# bottom-pcb.net
KiCad netlist of a schematic drawn in EAGLE
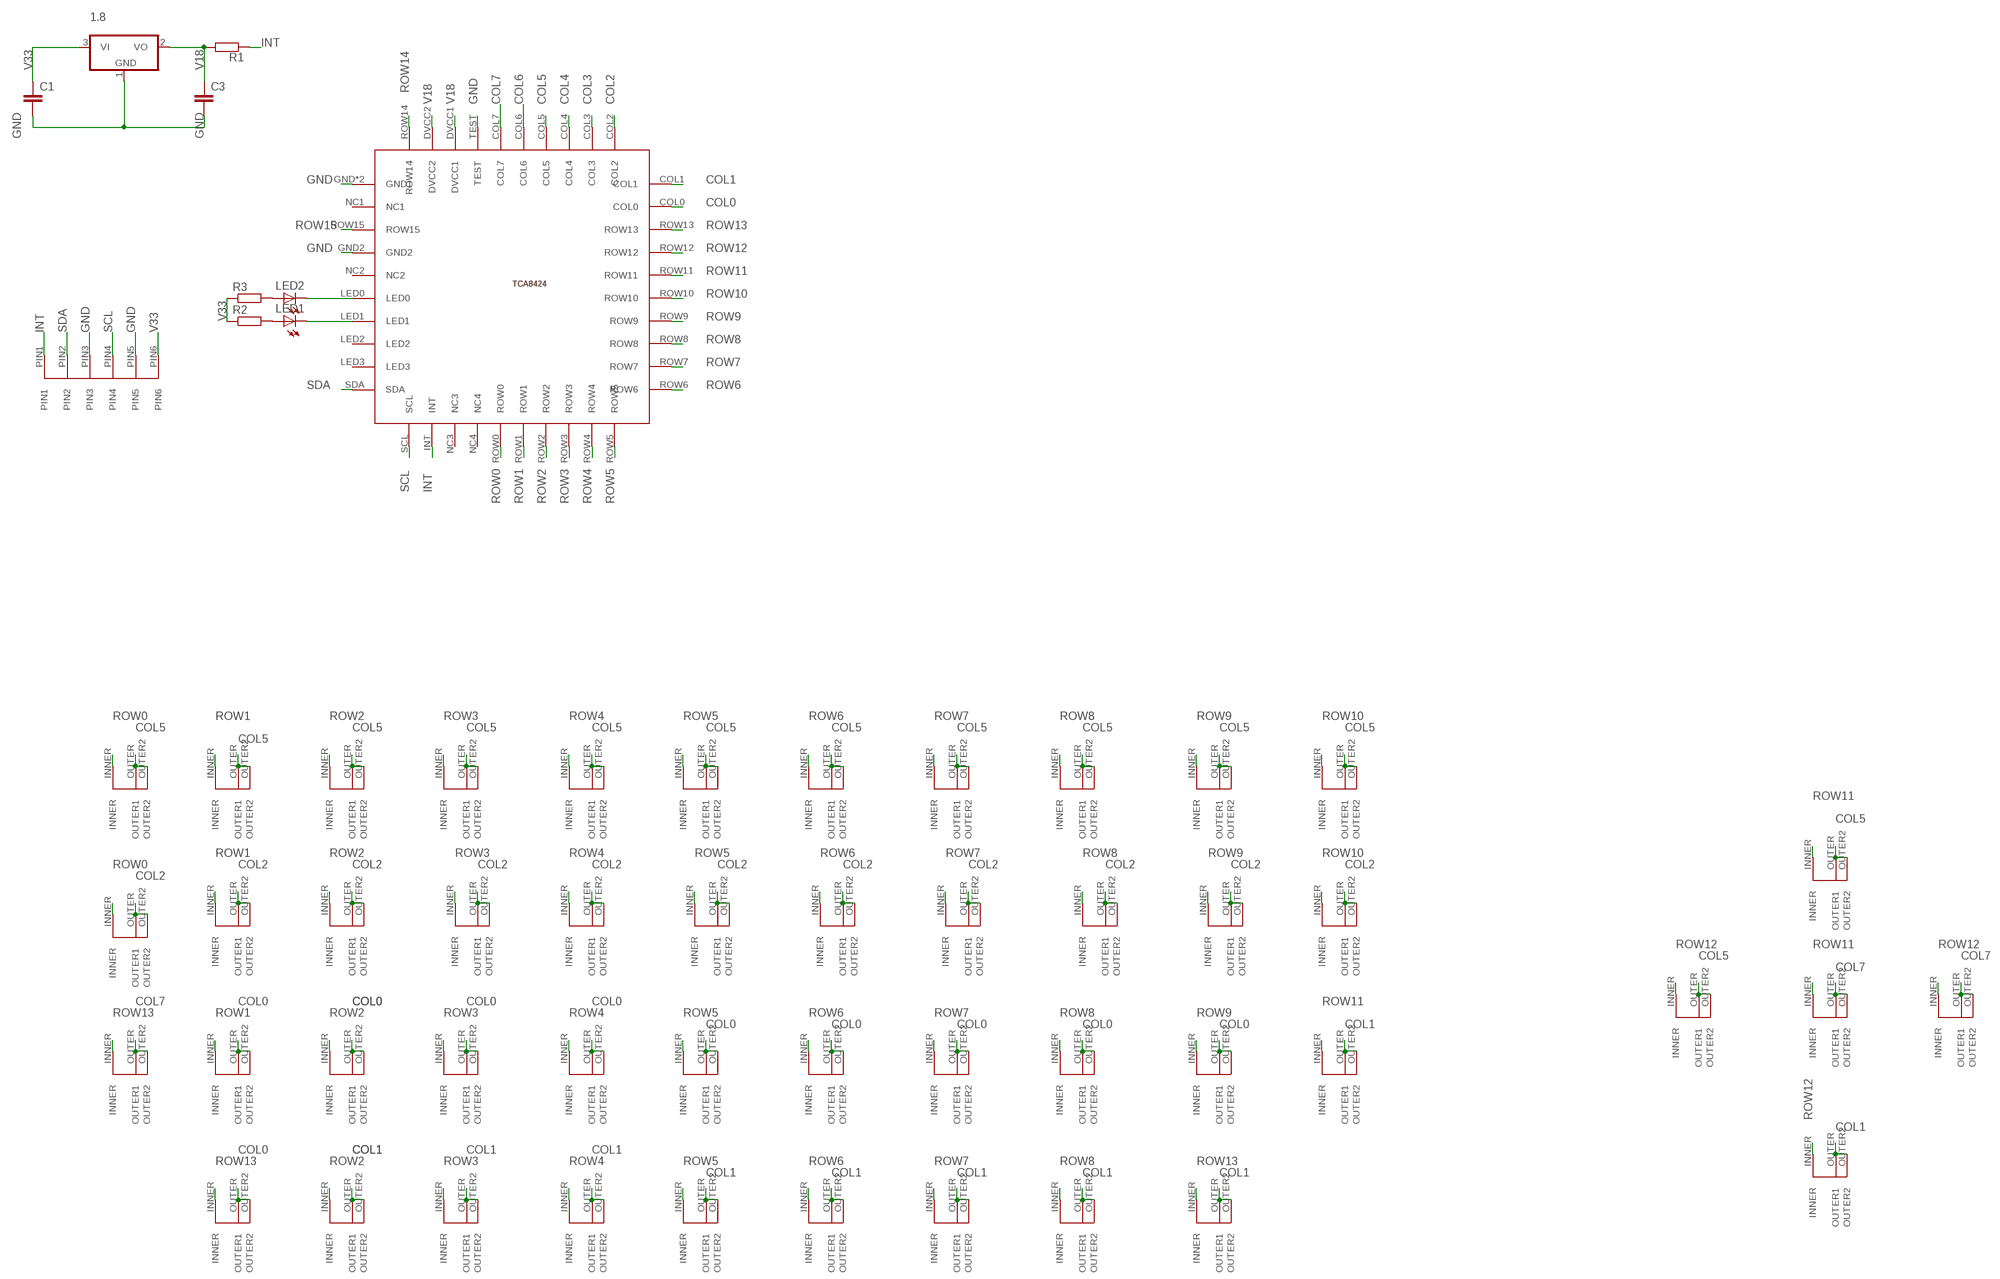
[diagram p0: schematic, sheet 1]

(export (version "E")
  (design (tool "Eeschema 10.0.6"))
  (components
    (comp (ref "1.8")
      (value "MCP1703CB")
      (footprint "eagle-import:SOT23")
      (libsource (lib "eagle-import") (part "MCP1703CB"))
    )
    (comp (ref "?")
      (value "BUTTON")
      (footprint "eagle-import:BUTTON")
      (libsource (lib "eagle-import") (part "BUTTON"))
    )
    (comp (ref "A")
      (value "BUTTON")
      (footprint "eagle-import:BUTTON")
      (libsource (lib "eagle-import") (part "BUTTON"))
    )
    (comp (ref "ARROWDOWN")
      (value "BUTTON")
      (footprint "eagle-import:BUTTON")
      (libsource (lib "eagle-import") (part "BUTTON"))
    )
    (comp (ref "ARROWLEFT")
      (value "BUTTON")
      (footprint "eagle-import:BUTTON")
      (libsource (lib "eagle-import") (part "BUTTON"))
    )
    (comp (ref "ARROWRIGHT")
      (value "BUTTON")
      (footprint "eagle-import:BUTTON")
      (libsource (lib "eagle-import") (part "BUTTON"))
    )
    (comp (ref "ARROWUP")
      (value "BUTTON")
      (footprint "eagle-import:BUTTON")
      (libsource (lib "eagle-import") (part "BUTTON"))
    )
    (comp (ref "AT")
      (value "BUTTON")
      (footprint "eagle-import:BUTTON")
      (libsource (lib "eagle-import") (part "BUTTON"))
    )
    (comp (ref "B")
      (value "BUTTON")
      (footprint "eagle-import:BUTTON")
      (libsource (lib "eagle-import") (part "BUTTON"))
    )
    (comp (ref "C")
      (value "BUTTON")
      (footprint "eagle-import:BUTTON")
      (libsource (lib "eagle-import") (part "BUTTON"))
    )
    (comp (ref "C1")
      (value "C-EUC0603")
      (footprint "eagle-import:C0603")
      (libsource (lib "eagle-import") (part "C-EUC0603"))
    )
    (comp (ref "C3")
      (value "C-EUC0603")
      (footprint "eagle-import:C0603")
      (libsource (lib "eagle-import") (part "C-EUC0603"))
    )
    (comp (ref "D")
      (value "BUTTON")
      (footprint "eagle-import:BUTTON")
      (libsource (lib "eagle-import") (part "BUTTON"))
    )
    (comp (ref "DEL")
      (value "BUTTON")
      (footprint "eagle-import:BUTTON")
      (libsource (lib "eagle-import") (part "BUTTON"))
    )
    (comp (ref "E3")
      (value "BUTTON")
      (footprint "eagle-import:BUTTON")
      (libsource (lib "eagle-import") (part "BUTTON"))
    )
    (comp (ref "ENTER")
      (value "BUTTON")
      (footprint "eagle-import:BUTTON")
      (libsource (lib "eagle-import") (part "BUTTON"))
    )
    (comp (ref "F")
      (value "BUTTON")
      (footprint "eagle-import:BUTTON")
      (libsource (lib "eagle-import") (part "BUTTON"))
    )
    (comp (ref "G")
      (value "BUTTON")
      (footprint "eagle-import:BUTTON")
      (libsource (lib "eagle-import") (part "BUTTON"))
    )
    (comp (ref "H")
      (value "BUTTON")
      (footprint "eagle-import:BUTTON")
      (libsource (lib "eagle-import") (part "BUTTON"))
    )
    (comp (ref "I8")
      (value "BUTTON")
      (footprint "eagle-import:BUTTON")
      (libsource (lib "eagle-import") (part "BUTTON"))
    )
    (comp (ref "J")
      (value "BUTTON")
      (footprint "eagle-import:BUTTON")
      (libsource (lib "eagle-import") (part "BUTTON"))
    )
    (comp (ref "K")
      (value "BUTTON")
      (footprint "eagle-import:BUTTON")
      (libsource (lib "eagle-import") (part "BUTTON"))
    )
    (comp (ref "KOMMA")
      (value "BUTTON")
      (footprint "eagle-import:BUTTON")
      (libsource (lib "eagle-import") (part "BUTTON"))
    )
    (comp (ref "L")
      (value "BUTTON")
      (footprint "eagle-import:BUTTON")
      (libsource (lib "eagle-import") (part "BUTTON"))
    )
    (comp (ref "LED1")
      (value "LEDCHIPLED_0603")
      (footprint "eagle-import:CHIPLED_0603")
      (libsource (lib "eagle-import") (part "LEDCHIPLED_0603"))
    )
    (comp (ref "LED2")
      (value "LEDCHIPLED_0603")
      (footprint "eagle-import:CHIPLED_0603")
      (libsource (lib "eagle-import") (part "LEDCHIPLED_0603"))
    )
    (comp (ref "LEFT-ALT")
      (value "BUTTON")
      (footprint "eagle-import:BUTTON")
      (libsource (lib "eagle-import") (part "BUTTON"))
    )
    (comp (ref "LIST")
      (value "BUTTON")
      (footprint "eagle-import:BUTTON")
      (libsource (lib "eagle-import") (part "BUTTON"))
    )
    (comp (ref "M")
      (value "BUTTON")
      (footprint "eagle-import:BUTTON")
      (libsource (lib "eagle-import") (part "BUTTON"))
    )
    (comp (ref "N")
      (value "BUTTON")
      (footprint "eagle-import:BUTTON")
      (libsource (lib "eagle-import") (part "BUTTON"))
    )
    (comp (ref "O9")
      (value "BUTTON")
      (footprint "eagle-import:BUTTON")
      (libsource (lib "eagle-import") (part "BUTTON"))
    )
    (comp (ref "OK")
      (value "BUTTON")
      (footprint "eagle-import:BUTTON")
      (libsource (lib "eagle-import") (part "BUTTON"))
    )
    (comp (ref "P0")
      (value "BUTTON")
      (footprint "eagle-import:BUTTON")
      (libsource (lib "eagle-import") (part "BUTTON"))
    )
    (comp (ref "PUNT")
      (value "BUTTON")
      (footprint "eagle-import:BUTTON")
      (libsource (lib "eagle-import") (part "BUTTON"))
    )
    (comp (ref "Q1")
      (value "BUTTON")
      (footprint "eagle-import:BUTTON")
      (libsource (lib "eagle-import") (part "BUTTON"))
    )
    (comp (ref "R1")
      (value "R-EU_R0603")
      (footprint "eagle-import:R0603")
      (libsource (lib "eagle-import") (part "resistor_R-EU_R0603"))
    )
    (comp (ref "R2")
      (value "R-EU_R0603")
      (footprint "eagle-import:R0603")
      (libsource (lib "eagle-import") (part "R-EU_R0603"))
    )
    (comp (ref "R3")
      (value "R-EU_R0603")
      (footprint "eagle-import:R0603")
      (libsource (lib "eagle-import") (part "R-EU_R0603"))
    )
    (comp (ref "R4")
      (value "BUTTON")
      (footprint "eagle-import:BUTTON")
      (libsource (lib "eagle-import") (part "BUTTON"))
    )
    (comp (ref "RIGHT-ALT")
      (value "BUTTON")
      (footprint "eagle-import:BUTTON")
      (libsource (lib "eagle-import") (part "BUTTON"))
    )
    (comp (ref "S")
      (value "BUTTON")
      (footprint "eagle-import:BUTTON")
      (libsource (lib "eagle-import") (part "BUTTON"))
    )
    (comp (ref "SEARCH")
      (value "BUTTON")
      (footprint "eagle-import:BUTTON")
      (libsource (lib "eagle-import") (part "BUTTON"))
    )
    (comp (ref "SHIFT")
      (value "BUTTON")
      (footprint "eagle-import:BUTTON")
      (libsource (lib "eagle-import") (part "BUTTON"))
    )
    (comp (ref "SHIFT2")
      (value "BUTTON")
      (footprint "eagle-import:BUTTON")
      (libsource (lib "eagle-import") (part "BUTTON"))
    )
    (comp (ref "SLASH")
      (value "BUTTON")
      (footprint "eagle-import:BUTTON")
      (libsource (lib "eagle-import") (part "BUTTON"))
    )
    (comp (ref "SPACE1")
      (value "BUTTON")
      (footprint "eagle-import:BUTTON")
      (libsource (lib "eagle-import") (part "BUTTON"))
    )
    (comp (ref "SPACE2")
      (value "BUTTON")
      (footprint "eagle-import:BUTTON")
      (libsource (lib "eagle-import") (part "BUTTON"))
    )
    (comp (ref "SPACE3")
      (value "BUTTON")
      (footprint "eagle-import:BUTTON")
      (libsource (lib "eagle-import") (part "BUTTON"))
    )
    (comp (ref "T5")
      (value "BUTTON")
      (footprint "eagle-import:BUTTON")
      (libsource (lib "eagle-import") (part "BUTTON"))
    )
    (comp (ref "TCA8424-1")
      (value "QFN40-TCA8424")
      (footprint "eagle-import:QFN40-TCA8424")
      (libsource (lib "eagle-import") (part "QFN40-TCA8424"))
    )
    (comp (ref "U$1")
      (value "6PCONNECTOR")
      (footprint "eagle-import:6PCONNECTOR")
      (libsource (lib "eagle-import") (part "6PCONNECTOR"))
    )
    (comp (ref "U7")
      (value "BUTTON")
      (footprint "eagle-import:BUTTON")
      (libsource (lib "eagle-import") (part "BUTTON"))
    )
    (comp (ref "V")
      (value "BUTTON")
      (footprint "eagle-import:BUTTON")
      (libsource (lib "eagle-import") (part "BUTTON"))
    )
    (comp (ref "W2")
      (value "BUTTON")
      (footprint "eagle-import:BUTTON")
      (libsource (lib "eagle-import") (part "BUTTON"))
    )
    (comp (ref "X")
      (value "BUTTON")
      (footprint "eagle-import:BUTTON")
      (libsource (lib "eagle-import") (part "BUTTON"))
    )
    (comp (ref "Y6")
      (value "BUTTON")
      (footprint "eagle-import:BUTTON")
      (libsource (lib "eagle-import") (part "BUTTON"))
    )
    (comp (ref "Z")
      (value "BUTTON")
      (footprint "eagle-import:BUTTON")
      (libsource (lib "eagle-import") (part "BUTTON"))
    )
  )
  (nets
    (net (code "1") (name "/COL0") (class "Default")
      (node (ref "B") (pin "OUTER") (pinfunction "OUTER1_OUTER") (pintype "bidirectional"))
      (node (ref "B") (pin "OUTER2") (pinfunction "OUTER2_OUTER2") (pintype "bidirectional"))
      (node (ref "C") (pin "OUTER") (pinfunction "OUTER1_OUTER") (pintype "bidirectional"))
      (node (ref "C") (pin "OUTER2") (pinfunction "OUTER2_OUTER2") (pintype "bidirectional"))
      (node (ref "KOMMA") (pin "OUTER") (pinfunction "OUTER1_OUTER") (pintype "bidirectional"))
      (node (ref "KOMMA") (pin "OUTER2") (pinfunction "OUTER2_OUTER2") (pintype "bidirectional"))
      (node (ref "LEFT-ALT") (pin "OUTER") (pinfunction "OUTER1_OUTER") (pintype "bidirectional"))
      (node (ref "LEFT-ALT") (pin "OUTER2") (pinfunction "OUTER2_OUTER2") (pintype "bidirectional"))
      (node (ref "M") (pin "OUTER") (pinfunction "OUTER1_OUTER") (pintype "bidirectional"))
      (node (ref "M") (pin "OUTER2") (pinfunction "OUTER2_OUTER2") (pintype "bidirectional"))
      (node (ref "N") (pin "OUTER") (pinfunction "OUTER1_OUTER") (pintype "bidirectional"))
      (node (ref "N") (pin "OUTER2") (pinfunction "OUTER2_OUTER2") (pintype "bidirectional"))
      (node (ref "PUNT") (pin "OUTER") (pinfunction "OUTER1_OUTER") (pintype "bidirectional"))
      (node (ref "PUNT") (pin "OUTER2") (pinfunction "OUTER2_OUTER2") (pintype "bidirectional"))
      (node (ref "TCA8424-1") (pin "COL0") (pinfunction "COL0_COL0") (pintype "bidirectional"))
      (node (ref "V") (pin "OUTER") (pinfunction "OUTER1_OUTER") (pintype "bidirectional"))
      (node (ref "V") (pin "OUTER2") (pinfunction "OUTER2_OUTER2") (pintype "bidirectional"))
      (node (ref "X") (pin "OUTER") (pinfunction "OUTER1_OUTER") (pintype "bidirectional"))
      (node (ref "X") (pin "OUTER2") (pinfunction "OUTER2_OUTER2") (pintype "bidirectional"))
      (node (ref "Z") (pin "OUTER") (pinfunction "OUTER1_OUTER") (pintype "bidirectional"))
      (node (ref "Z") (pin "OUTER2") (pinfunction "OUTER2_OUTER2") (pintype "bidirectional"))
    )
    (net (code "2") (name "/COL1") (class "Default")
      (node (ref "ARROWDOWN") (pin "OUTER") (pinfunction "OUTER1_OUTER") (pintype "bidirectional"))
      (node (ref "ARROWDOWN") (pin "OUTER2") (pinfunction "OUTER2_OUTER2") (pintype "bidirectional"))
      (node (ref "AT") (pin "OUTER") (pinfunction "OUTER1_OUTER") (pintype "bidirectional"))
      (node (ref "AT") (pin "OUTER2") (pinfunction "OUTER2_OUTER2") (pintype "bidirectional"))
      (node (ref "LIST") (pin "OUTER") (pinfunction "OUTER1_OUTER") (pintype "bidirectional"))
      (node (ref "LIST") (pin "OUTER2") (pinfunction "OUTER2_OUTER2") (pintype "bidirectional"))
      (node (ref "RIGHT-ALT") (pin "OUTER") (pinfunction "OUTER1_OUTER") (pintype "bidirectional"))
      (node (ref "RIGHT-ALT") (pin "OUTER2") (pinfunction "OUTER2_OUTER2") (pintype "bidirectional"))
      (node (ref "SEARCH") (pin "OUTER") (pinfunction "OUTER1_OUTER") (pintype "bidirectional"))
      (node (ref "SEARCH") (pin "OUTER2") (pinfunction "OUTER2_OUTER2") (pintype "bidirectional"))
      (node (ref "SHIFT2") (pin "OUTER") (pinfunction "OUTER1_OUTER") (pintype "bidirectional"))
      (node (ref "SHIFT2") (pin "OUTER2") (pinfunction "OUTER2_OUTER2") (pintype "bidirectional"))
      (node (ref "SLASH") (pin "OUTER") (pinfunction "OUTER1_OUTER") (pintype "bidirectional"))
      (node (ref "SLASH") (pin "OUTER2") (pinfunction "OUTER2_OUTER2") (pintype "bidirectional"))
      (node (ref "SPACE1") (pin "OUTER") (pinfunction "OUTER1_OUTER") (pintype "bidirectional"))
      (node (ref "SPACE1") (pin "OUTER2") (pinfunction "OUTER2_OUTER2") (pintype "bidirectional"))
      (node (ref "SPACE2") (pin "OUTER") (pinfunction "OUTER1_OUTER") (pintype "bidirectional"))
      (node (ref "SPACE2") (pin "OUTER2") (pinfunction "OUTER2_OUTER2") (pintype "bidirectional"))
      (node (ref "SPACE3") (pin "OUTER") (pinfunction "OUTER1_OUTER") (pintype "bidirectional"))
      (node (ref "SPACE3") (pin "OUTER2") (pinfunction "OUTER2_OUTER2") (pintype "bidirectional"))
      (node (ref "TCA8424-1") (pin "COL1") (pinfunction "COL1_COL1") (pintype "bidirectional"))
    )
    (net (code "3") (name "/COL2") (class "Default")
      (node (ref "?") (pin "OUTER") (pinfunction "OUTER1_OUTER") (pintype "bidirectional"))
      (node (ref "?") (pin "OUTER2") (pinfunction "OUTER2_OUTER2") (pintype "bidirectional"))
      (node (ref "A") (pin "OUTER") (pinfunction "OUTER1_OUTER") (pintype "bidirectional"))
      (node (ref "A") (pin "OUTER2") (pinfunction "OUTER2_OUTER2") (pintype "bidirectional"))
      (node (ref "D") (pin "OUTER") (pinfunction "OUTER1_OUTER") (pintype "bidirectional"))
      (node (ref "D") (pin "OUTER2") (pinfunction "OUTER2_OUTER2") (pintype "bidirectional"))
      (node (ref "ENTER") (pin "OUTER") (pinfunction "OUTER1_OUTER") (pintype "bidirectional"))
      (node (ref "ENTER") (pin "OUTER2") (pinfunction "OUTER2_OUTER2") (pintype "bidirectional"))
      (node (ref "F") (pin "OUTER") (pinfunction "OUTER1_OUTER") (pintype "bidirectional"))
      (node (ref "F") (pin "OUTER2") (pinfunction "OUTER2_OUTER2") (pintype "bidirectional"))
      (node (ref "G") (pin "OUTER") (pinfunction "OUTER1_OUTER") (pintype "bidirectional"))
      (node (ref "G") (pin "OUTER2") (pinfunction "OUTER2_OUTER2") (pintype "bidirectional"))
      (node (ref "H") (pin "OUTER") (pinfunction "OUTER1_OUTER") (pintype "bidirectional"))
      (node (ref "H") (pin "OUTER2") (pinfunction "OUTER2_OUTER2") (pintype "bidirectional"))
      (node (ref "J") (pin "OUTER") (pinfunction "OUTER1_OUTER") (pintype "bidirectional"))
      (node (ref "J") (pin "OUTER2") (pinfunction "OUTER2_OUTER2") (pintype "bidirectional"))
      (node (ref "K") (pin "OUTER") (pinfunction "OUTER1_OUTER") (pintype "bidirectional"))
      (node (ref "K") (pin "OUTER2") (pinfunction "OUTER2_OUTER2") (pintype "bidirectional"))
      (node (ref "L") (pin "OUTER") (pinfunction "OUTER1_OUTER") (pintype "bidirectional"))
      (node (ref "L") (pin "OUTER2") (pinfunction "OUTER2_OUTER2") (pintype "bidirectional"))
      (node (ref "S") (pin "OUTER") (pinfunction "OUTER1_OUTER") (pintype "bidirectional"))
      (node (ref "S") (pin "OUTER2") (pinfunction "OUTER2_OUTER2") (pintype "bidirectional"))
      (node (ref "TCA8424-1") (pin "COL2") (pinfunction "COL2_COL2") (pintype "bidirectional"))
    )
    (net (code "4") (name "/COL3") (class "Default")
      (node (ref "TCA8424-1") (pin "COL3") (pinfunction "COL3_COL3") (pintype "bidirectional"))
    )
    (net (code "5") (name "/COL4") (class "Default")
      (node (ref "TCA8424-1") (pin "COL4") (pinfunction "COL4_COL4") (pintype "bidirectional"))
    )
    (net (code "6") (name "/COL5") (class "Default")
      (node (ref "ARROWLEFT") (pin "OUTER") (pinfunction "OUTER1_OUTER") (pintype "bidirectional"))
      (node (ref "ARROWLEFT") (pin "OUTER2") (pinfunction "OUTER2_OUTER2") (pintype "bidirectional"))
      (node (ref "ARROWUP") (pin "OUTER") (pinfunction "OUTER1_OUTER") (pintype "bidirectional"))
      (node (ref "ARROWUP") (pin "OUTER2") (pinfunction "OUTER2_OUTER2") (pintype "bidirectional"))
      (node (ref "DEL") (pin "OUTER") (pinfunction "OUTER1_OUTER") (pintype "bidirectional"))
      (node (ref "DEL") (pin "OUTER2") (pinfunction "OUTER2_OUTER2") (pintype "bidirectional"))
      (node (ref "E3") (pin "OUTER") (pinfunction "OUTER1_OUTER") (pintype "bidirectional"))
      (node (ref "E3") (pin "OUTER2") (pinfunction "OUTER2_OUTER2") (pintype "bidirectional"))
      (node (ref "I8") (pin "OUTER") (pinfunction "OUTER1_OUTER") (pintype "bidirectional"))
      (node (ref "I8") (pin "OUTER2") (pinfunction "OUTER2_OUTER2") (pintype "bidirectional"))
      (node (ref "O9") (pin "OUTER") (pinfunction "OUTER1_OUTER") (pintype "bidirectional"))
      (node (ref "O9") (pin "OUTER2") (pinfunction "OUTER2_OUTER2") (pintype "bidirectional"))
      (node (ref "P0") (pin "OUTER") (pinfunction "OUTER1_OUTER") (pintype "bidirectional"))
      (node (ref "P0") (pin "OUTER2") (pinfunction "OUTER2_OUTER2") (pintype "bidirectional"))
      (node (ref "Q1") (pin "OUTER") (pinfunction "OUTER1_OUTER") (pintype "bidirectional"))
      (node (ref "Q1") (pin "OUTER2") (pinfunction "OUTER2_OUTER2") (pintype "bidirectional"))
      (node (ref "R4") (pin "OUTER") (pinfunction "OUTER1_OUTER") (pintype "bidirectional"))
      (node (ref "R4") (pin "OUTER2") (pinfunction "OUTER2_OUTER2") (pintype "bidirectional"))
      (node (ref "T5") (pin "OUTER") (pinfunction "OUTER1_OUTER") (pintype "bidirectional"))
      (node (ref "T5") (pin "OUTER2") (pinfunction "OUTER2_OUTER2") (pintype "bidirectional"))
      (node (ref "TCA8424-1") (pin "COL5") (pinfunction "COL5_COL5") (pintype "bidirectional"))
      (node (ref "U7") (pin "OUTER") (pinfunction "OUTER1_OUTER") (pintype "bidirectional"))
      (node (ref "U7") (pin "OUTER2") (pinfunction "OUTER2_OUTER2") (pintype "bidirectional"))
      (node (ref "W2") (pin "OUTER") (pinfunction "OUTER1_OUTER") (pintype "bidirectional"))
      (node (ref "W2") (pin "OUTER2") (pinfunction "OUTER2_OUTER2") (pintype "bidirectional"))
      (node (ref "Y6") (pin "OUTER") (pinfunction "OUTER1_OUTER") (pintype "bidirectional"))
      (node (ref "Y6") (pin "OUTER2") (pinfunction "OUTER2_OUTER2") (pintype "bidirectional"))
    )
    (net (code "7") (name "/COL6") (class "Default")
      (node (ref "TCA8424-1") (pin "COL6") (pinfunction "COL6_COL6") (pintype "bidirectional"))
    )
    (net (code "8") (name "/COL7") (class "Default")
      (node (ref "ARROWRIGHT") (pin "OUTER") (pinfunction "OUTER1_OUTER") (pintype "bidirectional"))
      (node (ref "ARROWRIGHT") (pin "OUTER2") (pinfunction "OUTER2_OUTER2") (pintype "bidirectional"))
      (node (ref "OK") (pin "OUTER") (pinfunction "OUTER1_OUTER") (pintype "bidirectional"))
      (node (ref "OK") (pin "OUTER2") (pinfunction "OUTER2_OUTER2") (pintype "bidirectional"))
      (node (ref "SHIFT") (pin "OUTER") (pinfunction "OUTER1_OUTER") (pintype "bidirectional"))
      (node (ref "SHIFT") (pin "OUTER2") (pinfunction "OUTER2_OUTER2") (pintype "bidirectional"))
      (node (ref "TCA8424-1") (pin "COL7") (pinfunction "COL7_COL7") (pintype "bidirectional"))
    )
    (net (code "9") (name "/GND") (class "Default")
      (node (ref "1.8") (pin "1") (pinfunction "GND_1") (pintype "passive"))
      (node (ref "C1") (pin "2") (pinfunction "2_2") (pintype "passive"))
      (node (ref "C3") (pin "2") (pinfunction "2_2") (pintype "passive"))
      (node (ref "TCA8424-1") (pin "GND") (pinfunction "GND1_GND") (pintype "bidirectional"))
      (node (ref "TCA8424-1") (pin "GND1") (pinfunction "GND1_GND1") (pintype "bidirectional"))
      (node (ref "TCA8424-1") (pin "GND2") (pinfunction "GND2_GND2") (pintype "bidirectional"))
      (node (ref "TCA8424-1") (pin "TEST") (pinfunction "TEST_TEST") (pintype "bidirectional"))
      (node (ref "U$1") (pin "PIN3") (pinfunction "PIN3_PIN3") (pintype "bidirectional"))
      (node (ref "U$1") (pin "PIN5") (pinfunction "PIN5_PIN5") (pintype "bidirectional"))
    )
    (net (code "10") (name "/INT") (class "Default")
      (node (ref "R1") (pin "1") (pinfunction "1_1") (pintype "passive"))
      (node (ref "TCA8424-1") (pin "INT") (pinfunction "INT_INT") (pintype "bidirectional"))
      (node (ref "U$1") (pin "PIN1") (pinfunction "PIN1_PIN1") (pintype "bidirectional"))
    )
    (net (code "11") (name "/ROW0") (class "Default")
      (node (ref "A") (pin "INNER") (pinfunction "INNER_INNER") (pintype "bidirectional"))
      (node (ref "Q1") (pin "INNER") (pinfunction "INNER_INNER") (pintype "bidirectional"))
      (node (ref "TCA8424-1") (pin "ROW0") (pinfunction "ROW0_ROW0") (pintype "bidirectional"))
    )
    (net (code "12") (name "/ROW1") (class "Default")
      (node (ref "S") (pin "INNER") (pinfunction "INNER_INNER") (pintype "bidirectional"))
      (node (ref "TCA8424-1") (pin "ROW1") (pinfunction "ROW1_ROW1") (pintype "bidirectional"))
      (node (ref "W2") (pin "INNER") (pinfunction "INNER_INNER") (pintype "bidirectional"))
      (node (ref "Z") (pin "INNER") (pinfunction "INNER_INNER") (pintype "bidirectional"))
    )
    (net (code "13") (name "/ROW2") (class "Default")
      (node (ref "D") (pin "INNER") (pinfunction "INNER_INNER") (pintype "bidirectional"))
      (node (ref "E3") (pin "INNER") (pinfunction "INNER_INNER") (pintype "bidirectional"))
      (node (ref "SEARCH") (pin "INNER") (pinfunction "INNER_INNER") (pintype "bidirectional"))
      (node (ref "TCA8424-1") (pin "ROW2") (pinfunction "ROW2_ROW2") (pintype "bidirectional"))
      (node (ref "X") (pin "INNER") (pinfunction "INNER_INNER") (pintype "bidirectional"))
    )
    (net (code "14") (name "/ROW3") (class "Default")
      (node (ref "AT") (pin "INNER") (pinfunction "INNER_INNER") (pintype "bidirectional"))
      (node (ref "C") (pin "INNER") (pinfunction "INNER_INNER") (pintype "bidirectional"))
      (node (ref "F") (pin "INNER") (pinfunction "INNER_INNER") (pintype "bidirectional"))
      (node (ref "R4") (pin "INNER") (pinfunction "INNER_INNER") (pintype "bidirectional"))
      (node (ref "TCA8424-1") (pin "ROW3") (pinfunction "ROW3_ROW3") (pintype "bidirectional"))
    )
    (net (code "15") (name "/ROW4") (class "Default")
      (node (ref "G") (pin "INNER") (pinfunction "INNER_INNER") (pintype "bidirectional"))
      (node (ref "SPACE1") (pin "INNER") (pinfunction "INNER_INNER") (pintype "bidirectional"))
      (node (ref "T5") (pin "INNER") (pinfunction "INNER_INNER") (pintype "bidirectional"))
      (node (ref "TCA8424-1") (pin "ROW4") (pinfunction "ROW4_ROW4") (pintype "bidirectional"))
      (node (ref "V") (pin "INNER") (pinfunction "INNER_INNER") (pintype "bidirectional"))
    )
    (net (code "16") (name "/ROW5") (class "Default")
      (node (ref "B") (pin "INNER") (pinfunction "INNER_INNER") (pintype "bidirectional"))
      (node (ref "H") (pin "INNER") (pinfunction "INNER_INNER") (pintype "bidirectional"))
      (node (ref "SPACE2") (pin "INNER") (pinfunction "INNER_INNER") (pintype "bidirectional"))
      (node (ref "TCA8424-1") (pin "ROW5") (pinfunction "ROW5_ROW5") (pintype "bidirectional"))
      (node (ref "Y6") (pin "INNER") (pinfunction "INNER_INNER") (pintype "bidirectional"))
    )
    (net (code "17") (name "/ROW6") (class "Default")
      (node (ref "J") (pin "INNER") (pinfunction "INNER_INNER") (pintype "bidirectional"))
      (node (ref "N") (pin "INNER") (pinfunction "INNER_INNER") (pintype "bidirectional"))
      (node (ref "SPACE3") (pin "INNER") (pinfunction "INNER_INNER") (pintype "bidirectional"))
      (node (ref "TCA8424-1") (pin "ROW6") (pinfunction "ROW6_ROW6") (pintype "bidirectional"))
      (node (ref "U7") (pin "INNER") (pinfunction "INNER_INNER") (pintype "bidirectional"))
    )
    (net (code "18") (name "/ROW7") (class "Default")
      (node (ref "I8") (pin "INNER") (pinfunction "INNER_INNER") (pintype "bidirectional"))
      (node (ref "K") (pin "INNER") (pinfunction "INNER_INNER") (pintype "bidirectional"))
      (node (ref "M") (pin "INNER") (pinfunction "INNER_INNER") (pintype "bidirectional"))
      (node (ref "SLASH") (pin "INNER") (pinfunction "INNER_INNER") (pintype "bidirectional"))
      (node (ref "TCA8424-1") (pin "ROW7") (pinfunction "ROW7_ROW7") (pintype "bidirectional"))
    )
    (net (code "19") (name "/ROW8") (class "Default")
      (node (ref "KOMMA") (pin "INNER") (pinfunction "INNER_INNER") (pintype "bidirectional"))
      (node (ref "L") (pin "INNER") (pinfunction "INNER_INNER") (pintype "bidirectional"))
      (node (ref "LIST") (pin "INNER") (pinfunction "INNER_INNER") (pintype "bidirectional"))
      (node (ref "O9") (pin "INNER") (pinfunction "INNER_INNER") (pintype "bidirectional"))
      (node (ref "TCA8424-1") (pin "ROW8") (pinfunction "ROW8_ROW8") (pintype "bidirectional"))
    )
    (net (code "20") (name "/ROW9") (class "Default")
      (node (ref "?") (pin "INNER") (pinfunction "INNER_INNER") (pintype "bidirectional"))
      (node (ref "P0") (pin "INNER") (pinfunction "INNER_INNER") (pintype "bidirectional"))
      (node (ref "PUNT") (pin "INNER") (pinfunction "INNER_INNER") (pintype "bidirectional"))
      (node (ref "TCA8424-1") (pin "ROW9") (pinfunction "ROW9_ROW9") (pintype "bidirectional"))
    )
    (net (code "21") (name "/ROW10") (class "Default")
      (node (ref "DEL") (pin "INNER") (pinfunction "INNER_INNER") (pintype "bidirectional"))
      (node (ref "ENTER") (pin "INNER") (pinfunction "INNER_INNER") (pintype "bidirectional"))
      (node (ref "TCA8424-1") (pin "ROW10") (pinfunction "ROW10_ROW10") (pintype "bidirectional"))
    )
    (net (code "22") (name "/ROW11") (class "Default")
      (node (ref "ARROWUP") (pin "INNER") (pinfunction "INNER_INNER") (pintype "bidirectional"))
      (node (ref "OK") (pin "INNER") (pinfunction "INNER_INNER") (pintype "bidirectional"))
      (node (ref "SHIFT2") (pin "INNER") (pinfunction "INNER_INNER") (pintype "bidirectional"))
      (node (ref "TCA8424-1") (pin "ROW11") (pinfunction "ROW11_ROW11") (pintype "bidirectional"))
    )
    (net (code "23") (name "/ROW12") (class "Default")
      (node (ref "ARROWDOWN") (pin "INNER") (pinfunction "INNER_INNER") (pintype "bidirectional"))
      (node (ref "ARROWLEFT") (pin "INNER") (pinfunction "INNER_INNER") (pintype "bidirectional"))
      (node (ref "ARROWRIGHT") (pin "INNER") (pinfunction "INNER_INNER") (pintype "bidirectional"))
      (node (ref "TCA8424-1") (pin "ROW12") (pinfunction "ROW12_ROW12") (pintype "bidirectional"))
    )
    (net (code "24") (name "/ROW13") (class "Default")
      (node (ref "LEFT-ALT") (pin "INNER") (pinfunction "INNER_INNER") (pintype "bidirectional"))
      (node (ref "RIGHT-ALT") (pin "INNER") (pinfunction "INNER_INNER") (pintype "bidirectional"))
      (node (ref "SHIFT") (pin "INNER") (pinfunction "INNER_INNER") (pintype "bidirectional"))
      (node (ref "TCA8424-1") (pin "ROW13") (pinfunction "ROW13_ROW13") (pintype "bidirectional"))
    )
    (net (code "25") (name "/ROW14") (class "Default")
      (node (ref "TCA8424-1") (pin "ROW14") (pinfunction "ROW14_ROW14") (pintype "bidirectional"))
    )
    (net (code "26") (name "/ROW15") (class "Default")
      (node (ref "TCA8424-1") (pin "ROW15") (pinfunction "ROW15_ROW15") (pintype "bidirectional"))
    )
    (net (code "27") (name "/SCL") (class "Default")
      (node (ref "TCA8424-1") (pin "SCL") (pinfunction "SCL_SCL") (pintype "bidirectional"))
      (node (ref "U$1") (pin "PIN4") (pinfunction "PIN4_PIN4") (pintype "bidirectional"))
    )
    (net (code "28") (name "/SDA") (class "Default")
      (node (ref "TCA8424-1") (pin "SDA") (pinfunction "SDA_SDA") (pintype "bidirectional"))
      (node (ref "U$1") (pin "PIN2") (pinfunction "PIN2_PIN2") (pintype "bidirectional"))
    )
    (net (code "29") (name "/V18") (class "Default")
      (node (ref "1.8") (pin "2") (pinfunction "VO_2") (pintype "passive"))
      (node (ref "C3") (pin "1") (pinfunction "1_1") (pintype "passive"))
      (node (ref "R1") (pin "2") (pinfunction "2_2") (pintype "passive"))
      (node (ref "TCA8424-1") (pin "DVCC1") (pinfunction "DVCC1_DVCC1") (pintype "bidirectional"))
      (node (ref "TCA8424-1") (pin "DVCC2") (pinfunction "DVCC2_DVCC2") (pintype "bidirectional"))
    )
    (net (code "30") (name "/V33") (class "Default")
      (node (ref "1.8") (pin "3") (pinfunction "VI_3") (pintype "input"))
      (node (ref "C1") (pin "1") (pinfunction "1_1") (pintype "passive"))
      (node (ref "R2") (pin "1") (pinfunction "1_1") (pintype "passive"))
      (node (ref "R3") (pin "1") (pinfunction "1_1") (pintype "passive"))
      (node (ref "U$1") (pin "PIN6") (pinfunction "PIN6_PIN6") (pintype "bidirectional"))
    )
    (net (code "31") (name "Net-(LED1-PadA)") (class "Default")
      (node (ref "LED1") (pin "A") (pinfunction "A_A") (pintype "passive"))
      (node (ref "R2") (pin "2") (pinfunction "2_2") (pintype "passive"))
    )
    (net (code "32") (name "Net-(LED1-PadC)") (class "Default")
      (node (ref "LED1") (pin "C") (pinfunction "C_C") (pintype "passive"))
      (node (ref "TCA8424-1") (pin "LED1") (pinfunction "LED1_LED1") (pintype "bidirectional"))
    )
    (net (code "33") (name "Net-(LED2-PadA)") (class "Default")
      (node (ref "LED2") (pin "A") (pinfunction "A_A") (pintype "passive"))
      (node (ref "R3") (pin "2") (pinfunction "2_2") (pintype "passive"))
    )
    (net (code "34") (name "Net-(LED2-PadC)") (class "Default")
      (node (ref "LED2") (pin "C") (pinfunction "C_C") (pintype "passive"))
      (node (ref "TCA8424-1") (pin "LED0") (pinfunction "LED0_LED0") (pintype "bidirectional"))
    )
    (net (code "35") (name "unconnected-(TCA8424-1-PadLED2)") (class "Default")
      (node (ref "TCA8424-1") (pin "LED2") (pinfunction "LED2_LED2") (pintype "bidirectional"))
    )
    (net (code "36") (name "unconnected-(TCA8424-1-PadLED3)") (class "Default")
      (node (ref "TCA8424-1") (pin "LED3") (pinfunction "LED3_LED3") (pintype "bidirectional"))
    )
    (net (code "37") (name "unconnected-(TCA8424-1-PadNC1)") (class "Default")
      (node (ref "TCA8424-1") (pin "NC1") (pinfunction "NC1_NC1") (pintype "bidirectional"))
    )
    (net (code "38") (name "unconnected-(TCA8424-1-PadNC2)") (class "Default")
      (node (ref "TCA8424-1") (pin "NC2") (pinfunction "NC2_NC2") (pintype "bidirectional"))
    )
    (net (code "39") (name "unconnected-(TCA8424-1-PadNC3)") (class "Default")
      (node (ref "TCA8424-1") (pin "NC3") (pinfunction "NC3_NC3") (pintype "bidirectional"))
    )
    (net (code "40") (name "unconnected-(TCA8424-1-PadNC4)") (class "Default")
      (node (ref "TCA8424-1") (pin "NC4") (pinfunction "NC4_NC4") (pintype "bidirectional"))
    )
  )
)
